# TX_RasPi_Ext_Sheet1.net
KiCad netlist of a schematic drawn in Altium Designer
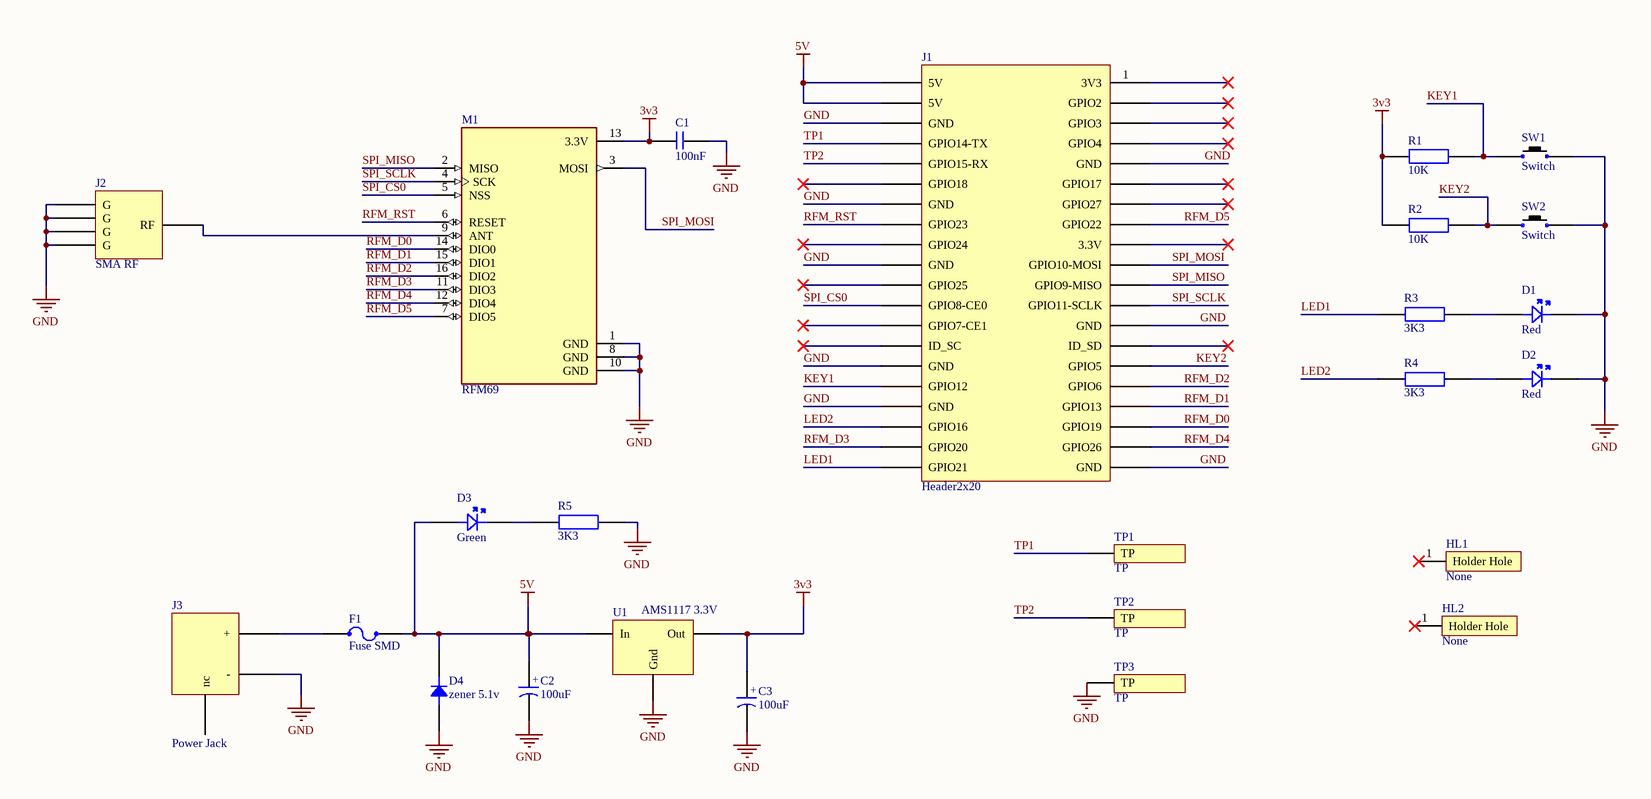
[diagram p0: TX_RasPi_Ext_Sheet1.SchDoc]

(export (version "E")
  (design (tool "Eeschema 10.0.6"))
  (components
    (comp (ref "C1")
      (value "100nF")
      (footprint "CAP_0805")
      (description "Capacitor SMD 0805")
      (libsource (lib "My_Integrated_Library") (part "Cap0805"))
    )
    (comp (ref "C2")
      (value "100uF")
      (footprint "Cap_Tan_Size_B")
      (description "Capacitor SMD Tantalium Size B")
      (libsource (lib "My_Integrated_Library") (part "Cap_Tant_B"))
    )
    (comp (ref "C3")
      (value "100uF")
      (footprint "Cap_Tan_Size_B")
      (description "Capacitor SMD Tantalium Size B")
      (libsource (lib "My_Integrated_Library") (part "Cap_Tant_B"))
    )
    (comp (ref "D1")
      (value "Red")
      (footprint "LED_0805_Red")
      (description "LED SMD 0805 Red")
      (libsource (lib "My_Integrated_Library") (part "LED_0805_Red"))
    )
    (comp (ref "D2")
      (value "Red")
      (footprint "LED_0805_Red")
      (description "LED SMD 0805 Red")
      (libsource (lib "My_Integrated_Library") (part "LED_0805_Red"))
    )
    (comp (ref "D3")
      (value "Green")
      (footprint "LED_0805_Green")
      (description "LED SMD 0805 Green")
      (libsource (lib "My_Integrated_Library") (part "LED_0805_Green"))
    )
    (comp (ref "D4")
      (value "zener 5.1v")
      (footprint "LL4148")
      (description "Diode SMD LL4148 1206")
      (libsource (lib "My_Integrated_Library") (part "Diode_LL4148"))
    )
    (comp (ref "F1")
      (value "Fuse SMD")
      (footprint "fuse_1206")
      (description "Fuse SMD 1206")
      (libsource (lib "My_Integrated_Library") (part "Fuse1206"))
    )
    (comp (ref "HL1")
      (value "None")
      (footprint "Holder_hole")
      (description "PCB Holder Hole")
      (libsource (lib "My_Integrated_Library") (part "Holder_Hole"))
    )
    (comp (ref "HL2")
      (value "None")
      (footprint "Holder_hole")
      (description "PCB Holder Hole")
      (libsource (lib "My_Integrated_Library") (part "Holder_Hole"))
    )
    (comp (ref "J1")
      (value "Header2x20")
      (footprint "Header_2x20_female")
      (description "Pin Header 2x20 pitch=2.54mm")
      (libsource (lib "My_Integrated_Library") (part "Header2x20"))
    )
    (comp (ref "J2")
      (value "SMA RF")
      (footprint "SMA_RF_RIGHT")
      (libsource (lib "My_Integrated_Library") (part "SMA_RF"))
    )
    (comp (ref "J3")
      (value "Power Jack")
      (footprint "power_jack_5mm")
      (libsource (lib "My_Integrated_Library") (part "power_jack_5mm"))
    )
    (comp (ref "M1")
      (value "RFM69")
      (footprint "RFM95W")
      (description "General ISM < 1GHz LoRaâ„¢ Transceiver Module 915MHz Surface Mount")
      (fields (field (name "MP") "RFM95W-915S2") (field (name "MF") "RF Solutions"))
      (libsource (lib "My_Integrated_Library") (part "RFM95W-915S2"))
    )
    (comp (ref "R1")
      (value "10K")
      (footprint "RES_0805")
      (description "Resistor SMD 0805")
      (libsource (lib "My_Integrated_Library") (part "Res0805"))
    )
    (comp (ref "R2")
      (value "10K")
      (footprint "RES_0805")
      (description "Resistor SMD 0805")
      (libsource (lib "My_Integrated_Library") (part "Res0805"))
    )
    (comp (ref "R3")
      (value "3K3")
      (footprint "RES_0805")
      (description "Resistor SMD 0805")
      (libsource (lib "My_Integrated_Library") (part "Res0805"))
    )
    (comp (ref "R4")
      (value "3K3")
      (footprint "RES_0805")
      (description "Resistor SMD 0805")
      (libsource (lib "My_Integrated_Library") (part "Res0805"))
    )
    (comp (ref "R5")
      (value "3K3")
      (footprint "RES_0805")
      (description "Resistor SMD 0805")
      (libsource (lib "My_Integrated_Library") (part "Res0805"))
    )
    (comp (ref "SW1")
      (value "Switch")
      (footprint "Tact_SW_SMD")
      (description "Tact switch SMD 2pin")
      (libsource (lib "My_Integrated_Library") (part "Tact_sw"))
    )
    (comp (ref "SW2")
      (value "Switch")
      (footprint "Tact_SW_SMD")
      (description "Tact switch SMD 2pin")
      (libsource (lib "My_Integrated_Library") (part "Tact_sw"))
    )
    (comp (ref "TP1")
      (value "TP")
      (footprint "TP")
      (description "Test point")
      (libsource (lib "My_Integrated_Library") (part "TP"))
    )
    (comp (ref "TP2")
      (value "TP")
      (footprint "TP")
      (description "Test point")
      (libsource (lib "My_Integrated_Library") (part "TP"))
    )
    (comp (ref "TP3")
      (value "TP")
      (footprint "TP")
      (description "Test point")
      (libsource (lib "My_Integrated_Library") (part "TP"))
    )
    (comp (ref "U1")
      (value "AMS1117 3.3V")
      (footprint "AMS1117-SOT223")
      (description "AMS1117 Regulator 3.3V SMD SOT223")
      (libsource (lib "My_Integrated_Library") (part "AMS1117-SOT223"))
    )
  )
  (nets
    (net (code "1") (name "/KEY1") (class "Default")
      (node (ref "J1") (pin "32") (pinfunction "GPIO12_32") (pintype "passive"))
      (node (ref "R1") (pin "2") (pinfunction "2_2") (pintype "passive"))
      (node (ref "SW1") (pin "2") (pinfunction "2_2") (pintype "passive"))
    )
    (net (code "2") (name "/KEY2") (class "Default")
      (node (ref "J1") (pin "29") (pinfunction "GPIO5_29") (pintype "passive"))
      (node (ref "R2") (pin "2") (pinfunction "2_2") (pintype "passive"))
      (node (ref "SW2") (pin "2") (pinfunction "2_2") (pintype "passive"))
    )
    (net (code "3") (name "/LED1") (class "Default")
      (node (ref "J1") (pin "40") (pinfunction "GPIO21_40") (pintype "passive"))
      (node (ref "R3") (pin "1") (pinfunction "1_1") (pintype "passive"))
    )
    (net (code "4") (name "/LED2") (class "Default")
      (node (ref "J1") (pin "36") (pinfunction "GPIO16_36") (pintype "passive"))
      (node (ref "R4") (pin "1") (pinfunction "1_1") (pintype "passive"))
    )
    (net (code "5") (name "/RFM_D0") (class "Default")
      (node (ref "J1") (pin "35") (pinfunction "GPIO19_35") (pintype "passive"))
      (node (ref "M1") (pin "14") (pinfunction "DIO0_14") (pintype "bidirectional"))
    )
    (net (code "6") (name "/RFM_D1") (class "Default")
      (node (ref "J1") (pin "33") (pinfunction "GPIO13_33") (pintype "passive"))
      (node (ref "M1") (pin "15") (pinfunction "DIO1_15") (pintype "bidirectional"))
    )
    (net (code "7") (name "/RFM_D2") (class "Default")
      (node (ref "J1") (pin "31") (pinfunction "GPIO6_31") (pintype "passive"))
      (node (ref "M1") (pin "16") (pinfunction "DIO2_16") (pintype "bidirectional"))
    )
    (net (code "8") (name "/RFM_D3") (class "Default")
      (node (ref "J1") (pin "38") (pinfunction "GPIO20_38") (pintype "passive"))
      (node (ref "M1") (pin "11") (pinfunction "DIO3_11") (pintype "bidirectional"))
    )
    (net (code "9") (name "/RFM_D4") (class "Default")
      (node (ref "J1") (pin "37") (pinfunction "GPIO26_37") (pintype "passive"))
      (node (ref "M1") (pin "12") (pinfunction "DIO4_12") (pintype "bidirectional"))
    )
    (net (code "10") (name "/RFM_D5") (class "Default")
      (node (ref "J1") (pin "15") (pinfunction "GPIO22_15") (pintype "passive"))
      (node (ref "M1") (pin "7") (pinfunction "DIO5_7") (pintype "bidirectional"))
    )
    (net (code "11") (name "/RFM_RST") (class "Default")
      (node (ref "J1") (pin "16") (pinfunction "GPIO23_16") (pintype "passive"))
      (node (ref "M1") (pin "6") (pinfunction "RESET_6") (pintype "bidirectional"))
    )
    (net (code "12") (name "/SPI_CS0") (class "Default")
      (node (ref "J1") (pin "24") (pinfunction "GPIO8-CE0_24") (pintype "passive"))
      (node (ref "M1") (pin "5") (pinfunction "NSS_5") (pintype "input"))
    )
    (net (code "13") (name "/SPI_MISO") (class "Default")
      (node (ref "J1") (pin "21") (pinfunction "GPIO9-MISO_21") (pintype "passive"))
      (node (ref "M1") (pin "2") (pinfunction "MISO_2") (pintype "input"))
    )
    (net (code "14") (name "/SPI_MOSI") (class "Default")
      (node (ref "J1") (pin "19") (pinfunction "GPIO10-MOSI_19") (pintype "passive"))
      (node (ref "M1") (pin "3") (pinfunction "MOSI_3") (pintype "output"))
    )
    (net (code "15") (name "/SPI_SCLK") (class "Default")
      (node (ref "J1") (pin "23") (pinfunction "GPIO11-SCLK_23") (pintype "passive"))
      (node (ref "M1") (pin "4") (pinfunction "SCK_4") (pintype "input"))
    )
    (net (code "16") (name "/TP1") (class "Default")
      (node (ref "J1") (pin "8") (pinfunction "GPIO14-TX_8") (pintype "passive"))
      (node (ref "TP1") (pin "1") (pinfunction "TP_1") (pintype "passive"))
    )
    (net (code "17") (name "/TP2") (class "Default")
      (node (ref "J1") (pin "10") (pinfunction "GPIO15-RX_10") (pintype "passive"))
      (node (ref "TP2") (pin "1") (pinfunction "TP_1") (pintype "passive"))
    )
    (net (code "18") (name "3v3") (class "Default")
      (node (ref "C1") (pin "2") (pinfunction "2_2") (pintype "passive"))
      (node (ref "C3") (pin "+") (pinfunction "+_+") (pintype "passive"))
      (node (ref "M1") (pin "13") (pinfunction "3.3V_13") (pintype "power_in"))
      (node (ref "R1") (pin "1") (pinfunction "1_1") (pintype "passive"))
      (node (ref "R2") (pin "1") (pinfunction "1_1") (pintype "passive"))
      (node (ref "U1") (pin "3") (pinfunction "Out_3") (pintype "passive"))
    )
    (net (code "19") (name "5V") (class "Default")
      (node (ref "C2") (pin "+") (pinfunction "+_+") (pintype "passive"))
      (node (ref "D3") (pin "1") (pinfunction "1_1") (pintype "passive"))
      (node (ref "D4") (pin "K") (pinfunction "K_K") (pintype "passive"))
      (node (ref "F1") (pin "1") (pinfunction "1_1") (pintype "passive"))
      (node (ref "J1") (pin "2") (pinfunction "5V_2") (pintype "passive"))
      (node (ref "J1") (pin "4") (pinfunction "5V_4") (pintype "passive"))
      (node (ref "U1") (pin "1") (pinfunction "In_1") (pintype "passive"))
    )
    (net (code "20") (name "GND") (class "Default")
      (node (ref "C1") (pin "1") (pinfunction "1_1") (pintype "passive"))
      (node (ref "C2") (pin "-") (pinfunction "-_-") (pintype "passive"))
      (node (ref "C3") (pin "-") (pinfunction "-_-") (pintype "passive"))
      (node (ref "D1") (pin "2") (pinfunction "2_2") (pintype "passive"))
      (node (ref "D2") (pin "2") (pinfunction "2_2") (pintype "passive"))
      (node (ref "D4") (pin "A") (pinfunction "A_A") (pintype "passive"))
      (node (ref "J1") (pin "14") (pinfunction "GND_14") (pintype "passive"))
      (node (ref "J1") (pin "20") (pinfunction "GND_20") (pintype "passive"))
      (node (ref "J1") (pin "25") (pinfunction "GND_25") (pintype "passive"))
      (node (ref "J1") (pin "30") (pinfunction "GND_30") (pintype "passive"))
      (node (ref "J1") (pin "34") (pinfunction "GND_34") (pintype "passive"))
      (node (ref "J1") (pin "39") (pinfunction "GND_39") (pintype "passive"))
      (node (ref "J1") (pin "6") (pinfunction "GND_6") (pintype "passive"))
      (node (ref "J1") (pin "9") (pinfunction "GND_9") (pintype "passive"))
      (node (ref "J2") (pin "2") (pinfunction "G_2") (pintype "passive"))
      (node (ref "J2") (pin "3") (pinfunction "G_3") (pintype "passive"))
      (node (ref "J2") (pin "4") (pinfunction "G_4") (pintype "passive"))
      (node (ref "J2") (pin "5") (pinfunction "G_5") (pintype "passive"))
      (node (ref "J3") (pin "1") (pinfunction "-_1") (pintype "passive"))
      (node (ref "M1") (pin "1") (pinfunction "GND_1") (pintype "power_in"))
      (node (ref "M1") (pin "10") (pinfunction "GND_10") (pintype "power_in"))
      (node (ref "M1") (pin "8") (pinfunction "GND_8") (pintype "power_in"))
      (node (ref "R5") (pin "2") (pinfunction "2_2") (pintype "passive"))
      (node (ref "SW1") (pin "1") (pinfunction "1_1") (pintype "passive"))
      (node (ref "SW2") (pin "1") (pinfunction "1_1") (pintype "passive"))
      (node (ref "TP3") (pin "1") (pinfunction "TP_1") (pintype "passive"))
      (node (ref "U1") (pin "2") (pinfunction "Gnd_2") (pintype "passive"))
    )
    (net (code "21") (name "Net-(D1-Pad1)") (class "Default")
      (node (ref "D1") (pin "1") (pinfunction "1_1") (pintype "passive"))
      (node (ref "R3") (pin "2") (pinfunction "2_2") (pintype "passive"))
    )
    (net (code "22") (name "Net-(D2-Pad1)") (class "Default")
      (node (ref "D2") (pin "1") (pinfunction "1_1") (pintype "passive"))
      (node (ref "R4") (pin "2") (pinfunction "2_2") (pintype "passive"))
    )
    (net (code "23") (name "Net-(D3-Pad2)") (class "Default")
      (node (ref "D3") (pin "2") (pinfunction "2_2") (pintype "passive"))
      (node (ref "R5") (pin "1") (pinfunction "1_1") (pintype "passive"))
    )
    (net (code "24") (name "Net-(J2-RF)") (class "Default")
      (node (ref "J2") (pin "1") (pinfunction "RF_1") (pintype "passive"))
      (node (ref "M1") (pin "9") (pinfunction "ANT_9") (pintype "bidirectional"))
    )
    (net (code "25") (name "Net-(J3-+)") (class "Default")
      (node (ref "F1") (pin "2") (pinfunction "2_2") (pintype "passive"))
      (node (ref "J3") (pin "2") (pinfunction "+_2") (pintype "passive"))
    )
    (net (code "26") (name "unconnected-(HL1-Holder_Hole-Pad1)") (class "Default")
      (node (ref "HL1") (pin "1") (pinfunction "Holder_Hole_1") (pintype "passive+no_connect"))
    )
    (net (code "27") (name "unconnected-(HL2-Holder_Hole-Pad1)") (class "Default")
      (node (ref "HL2") (pin "1") (pinfunction "Holder_Hole_1") (pintype "passive+no_connect"))
    )
    (net (code "28") (name "unconnected-(J1-3.3V-Pad17)") (class "Default")
      (node (ref "J1") (pin "17") (pinfunction "3.3V_17") (pintype "passive+no_connect"))
    )
    (net (code "29") (name "unconnected-(J1-3V3-Pad1)") (class "Default")
      (node (ref "J1") (pin "1") (pinfunction "3V3_1") (pintype "passive+no_connect"))
    )
    (net (code "30") (name "unconnected-(J1-GPIO2-Pad3)") (class "Default")
      (node (ref "J1") (pin "3") (pinfunction "GPIO2_3") (pintype "passive+no_connect"))
    )
    (net (code "31") (name "unconnected-(J1-GPIO3-Pad5)") (class "Default")
      (node (ref "J1") (pin "5") (pinfunction "GPIO3_5") (pintype "passive+no_connect"))
    )
    (net (code "32") (name "unconnected-(J1-GPIO4-Pad7)") (class "Default")
      (node (ref "J1") (pin "7") (pinfunction "GPIO4_7") (pintype "passive+no_connect"))
    )
    (net (code "33") (name "unconnected-(J1-GPIO7-CE1-Pad26)") (class "Default")
      (node (ref "J1") (pin "26") (pinfunction "GPIO7-CE1_26") (pintype "passive+no_connect"))
    )
    (net (code "34") (name "unconnected-(J1-GPIO17-Pad11)") (class "Default")
      (node (ref "J1") (pin "11") (pinfunction "GPIO17_11") (pintype "passive+no_connect"))
    )
    (net (code "35") (name "unconnected-(J1-GPIO18-Pad12)") (class "Default")
      (node (ref "J1") (pin "12") (pinfunction "GPIO18_12") (pintype "passive+no_connect"))
    )
    (net (code "36") (name "unconnected-(J1-GPIO24-Pad18)") (class "Default")
      (node (ref "J1") (pin "18") (pinfunction "GPIO24_18") (pintype "passive+no_connect"))
    )
    (net (code "37") (name "unconnected-(J1-GPIO25-Pad22)") (class "Default")
      (node (ref "J1") (pin "22") (pinfunction "GPIO25_22") (pintype "passive+no_connect"))
    )
    (net (code "38") (name "unconnected-(J1-GPIO27-Pad13)") (class "Default")
      (node (ref "J1") (pin "13") (pinfunction "GPIO27_13") (pintype "passive+no_connect"))
    )
    (net (code "39") (name "unconnected-(J1-ID_SC-Pad28)") (class "Default")
      (node (ref "J1") (pin "28") (pinfunction "ID_SC_28") (pintype "passive+no_connect"))
    )
    (net (code "40") (name "unconnected-(J1-ID_SD-Pad27)") (class "Default")
      (node (ref "J1") (pin "27") (pinfunction "ID_SD_27") (pintype "passive+no_connect"))
    )
    (net (code "41") (name "unconnected-(J3-nc-Pad3)") (class "Default")
      (node (ref "J3") (pin "3") (pinfunction "nc_3") (pintype "passive"))
    )
  )
)
